# sockets.net
KiCad netlist of a schematic drawn in Altium Designer
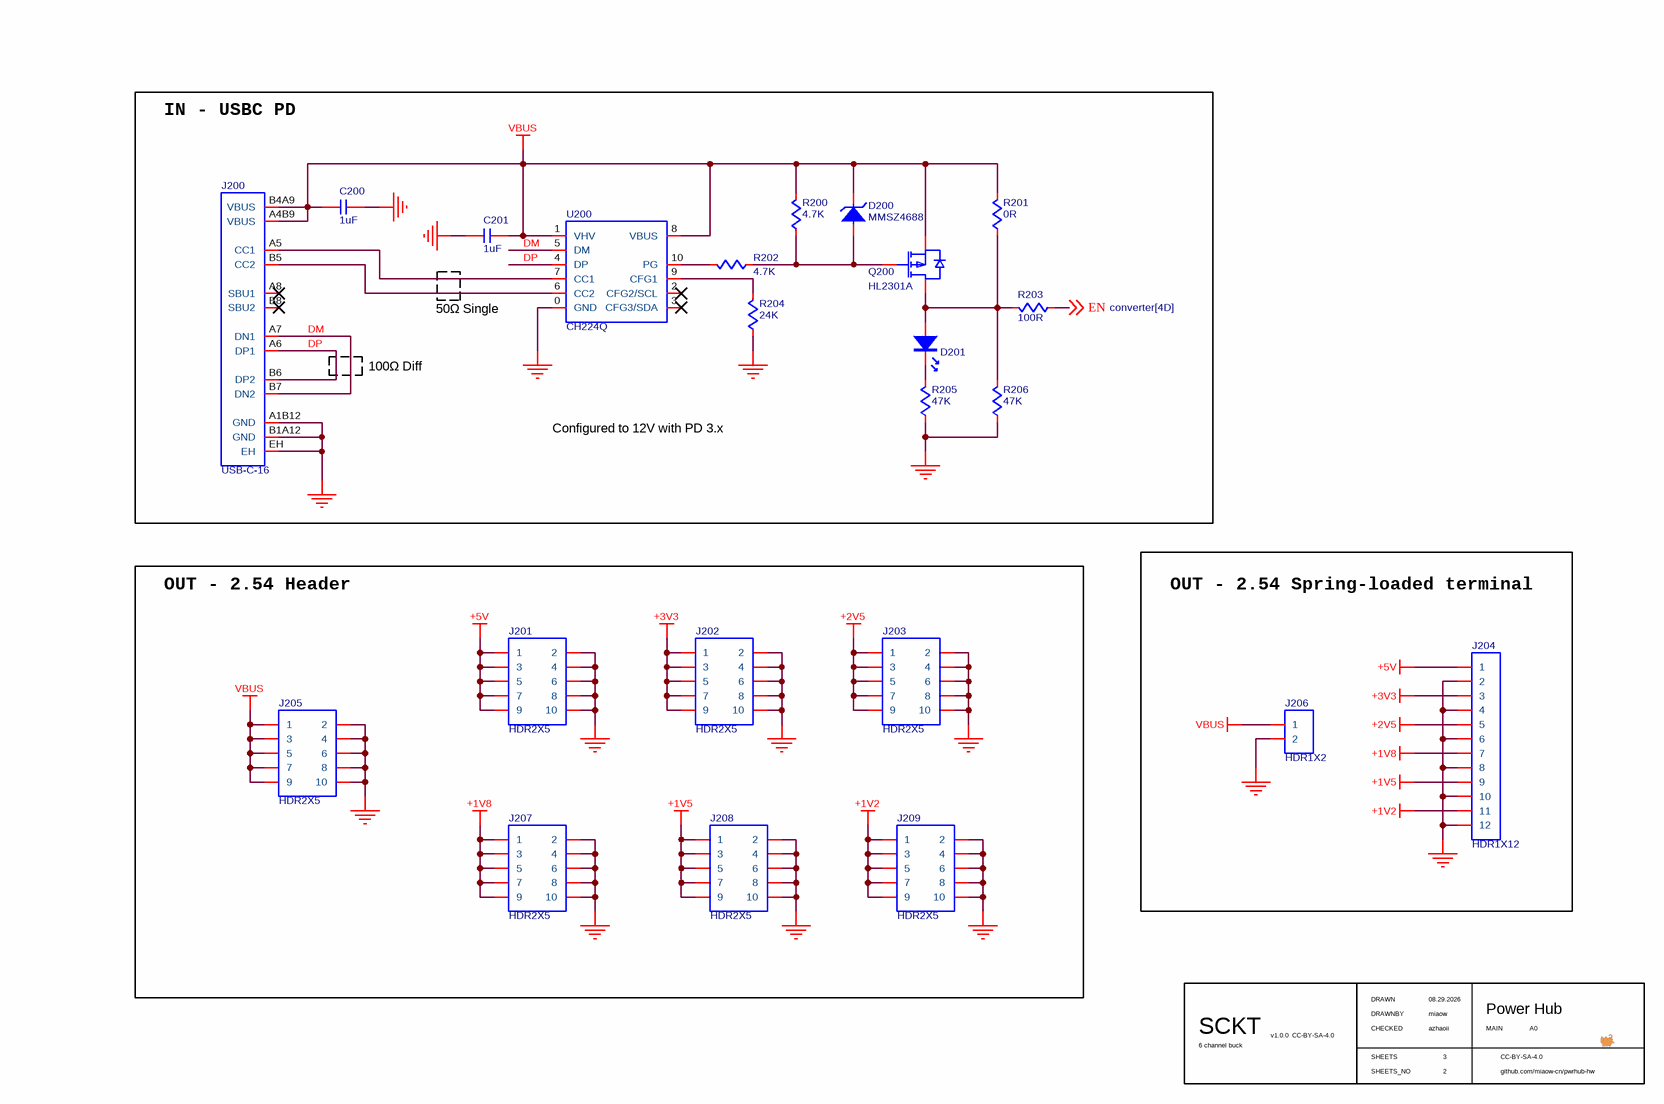
[diagram p0: sockets.schdoc]

(export (version "E")
  (design (tool "Eeschema 10.0.6"))
  (components
    (comp (ref "C200")
      (value "1uF")
      (footprint "mw:C0402")
      (fields (field (name "VOLTAGE") "25V") (field (name "Comment") "C-NOMO"))
      (libsource (lib "mw") (part "C-NOMO"))
    )
    (comp (ref "C201")
      (value "1uF")
      (footprint "mw:C0402")
      (fields (field (name "VOLTAGE") "25V") (field (name "Comment") "C-NOMO"))
      (libsource (lib "mw") (part "C-NOMO"))
    )
    (comp (ref "D200")
      (value "MMSZ4688")
      (footprint "mw:MMSZ4688")
      (description "ZENER")
      (libsource (lib "mw") (part "MMSZ4688"))
    )
    (comp (ref "D201") (value "LED") (footprint "mw:LED0603") (libsource (lib "mw") (part "LED")))
    (comp (ref "J200") (value "USB-C-16") (footprint "mw:USB-C-16") (libsource (lib "mw") (part "USB-C-16")))
    (comp (ref "J201") (value "HDR2X5") (footprint "mw:HDR2X5") (libsource (lib "mw") (part "HDR2X5")))
    (comp (ref "J202") (value "HDR2X5") (footprint "mw:HDR2X5") (libsource (lib "mw") (part "HDR2X5")))
    (comp (ref "J203") (value "HDR2X5") (footprint "mw:HDR2X5") (libsource (lib "mw") (part "HDR2X5")))
    (comp (ref "J204")
      (value "HDR1X12")
      (footprint "mw:KF141R-2.54-12P")
      (libsource (lib "mw") (part "HDR1X12"))
    )
    (comp (ref "J205") (value "HDR2X5") (footprint "mw:HDR2X5") (libsource (lib "mw") (part "HDR2X5")))
    (comp (ref "J206")
      (value "HDR1X2")
      (footprint "mw:KF141R-2.54-2P")
      (libsource (lib "mw") (part "HDR1X2"))
    )
    (comp (ref "J207") (value "HDR2X5") (footprint "mw:HDR2X5") (libsource (lib "mw") (part "HDR2X5")))
    (comp (ref "J208") (value "HDR2X5") (footprint "mw:HDR2X5") (libsource (lib "mw") (part "HDR2X5")))
    (comp (ref "J209") (value "HDR2X5") (footprint "mw:HDR2X5") (libsource (lib "mw") (part "HDR2X5")))
    (comp (ref "Q200")
      (value "HL2301A")
      (footprint "mw:HL2301A")
      (description "PMOS")
      (libsource (lib "mw") (part "HL2301A"))
    )
    (comp (ref "R200")
      (value "4.7K")
      (footprint "mw:R0402")
      (fields (field (name "Comment") "R"))
      (libsource (lib "mw") (part "R"))
    )
    (comp (ref "R201")
      (value "0R")
      (footprint "mw:R0402")
      (fields (field (name "Comment") "R"))
      (libsource (lib "mw") (part "R"))
    )
    (comp (ref "R202")
      (value "4.7K")
      (footprint "mw:R0402")
      (fields (field (name "Comment") "R"))
      (libsource (lib "mw") (part "R"))
    )
    (comp (ref "R203")
      (value "100R")
      (footprint "mw:R0402")
      (fields (field (name "Comment") "R"))
      (libsource (lib "mw") (part "R"))
    )
    (comp (ref "R204")
      (value "24K")
      (footprint "mw:R0402")
      (fields (field (name "Comment") "R"))
      (libsource (lib "mw") (part "R"))
    )
    (comp (ref "R205")
      (value "47K")
      (footprint "mw:R0402")
      (fields (field (name "Comment") "R"))
      (libsource (lib "mw") (part "R"))
    )
    (comp (ref "R206")
      (value "47K")
      (footprint "mw:R0402")
      (fields (field (name "Comment") "R"))
      (libsource (lib "mw") (part "R"))
    )
    (comp (ref "U200")
      (value "CH224Q")
      (footprint "mw:CH224Q")
      (description "PD3.2")
      (libsource (lib "mw") (part "CH224Q"))
    )
  )
  (nets
    (net (code "1") (name "+1V2") (class "Default")
      (node (ref "J204") (pin "11") (pinfunction "11_11") (pintype "passive"))
      (node (ref "J209") (pin "1") (pinfunction "1_1") (pintype "passive"))
      (node (ref "J209") (pin "3") (pinfunction "3_3") (pintype "passive"))
      (node (ref "J209") (pin "5") (pinfunction "5_5") (pintype "passive"))
      (node (ref "J209") (pin "7") (pinfunction "7_7") (pintype "passive"))
      (node (ref "J209") (pin "9") (pinfunction "9_9") (pintype "passive"))
    )
    (net (code "2") (name "+1V5") (class "Default")
      (node (ref "J204") (pin "9") (pinfunction "9_9") (pintype "passive"))
      (node (ref "J208") (pin "1") (pinfunction "1_1") (pintype "passive"))
      (node (ref "J208") (pin "3") (pinfunction "3_3") (pintype "passive"))
      (node (ref "J208") (pin "5") (pinfunction "5_5") (pintype "passive"))
      (node (ref "J208") (pin "7") (pinfunction "7_7") (pintype "passive"))
      (node (ref "J208") (pin "9") (pinfunction "9_9") (pintype "passive"))
    )
    (net (code "3") (name "+1V8") (class "Default")
      (node (ref "J204") (pin "7") (pinfunction "7_7") (pintype "passive"))
      (node (ref "J207") (pin "1") (pinfunction "1_1") (pintype "passive"))
      (node (ref "J207") (pin "3") (pinfunction "3_3") (pintype "passive"))
      (node (ref "J207") (pin "5") (pinfunction "5_5") (pintype "passive"))
      (node (ref "J207") (pin "7") (pinfunction "7_7") (pintype "passive"))
      (node (ref "J207") (pin "9") (pinfunction "9_9") (pintype "passive"))
    )
    (net (code "4") (name "+2V5") (class "Default")
      (node (ref "J203") (pin "1") (pinfunction "1_1") (pintype "passive"))
      (node (ref "J203") (pin "3") (pinfunction "3_3") (pintype "passive"))
      (node (ref "J203") (pin "5") (pinfunction "5_5") (pintype "passive"))
      (node (ref "J203") (pin "7") (pinfunction "7_7") (pintype "passive"))
      (node (ref "J203") (pin "9") (pinfunction "9_9") (pintype "passive"))
      (node (ref "J204") (pin "5") (pinfunction "5_5") (pintype "passive"))
    )
    (net (code "5") (name "+3V3") (class "Default")
      (node (ref "J202") (pin "1") (pinfunction "1_1") (pintype "passive"))
      (node (ref "J202") (pin "3") (pinfunction "3_3") (pintype "passive"))
      (node (ref "J202") (pin "5") (pinfunction "5_5") (pintype "passive"))
      (node (ref "J202") (pin "7") (pinfunction "7_7") (pintype "passive"))
      (node (ref "J202") (pin "9") (pinfunction "9_9") (pintype "passive"))
      (node (ref "J204") (pin "3") (pinfunction "3_3") (pintype "passive"))
    )
    (net (code "6") (name "+5V") (class "Default")
      (node (ref "J201") (pin "1") (pinfunction "1_1") (pintype "passive"))
      (node (ref "J201") (pin "3") (pinfunction "3_3") (pintype "passive"))
      (node (ref "J201") (pin "5") (pinfunction "5_5") (pintype "passive"))
      (node (ref "J201") (pin "7") (pinfunction "7_7") (pintype "passive"))
      (node (ref "J201") (pin "9") (pinfunction "9_9") (pintype "passive"))
      (node (ref "J204") (pin "1") (pinfunction "1_1") (pintype "passive"))
    )
    (net (code "7") (name "/DM") (class "Default")
      (node (ref "J200") (pin "A7") (pinfunction "DN1_A7") (pintype "passive"))
      (node (ref "J200") (pin "B7") (pinfunction "DN2_B7") (pintype "passive"))
      (node (ref "U200") (pin "5") (pinfunction "DM_5") (pintype "passive"))
    )
    (net (code "8") (name "/DP") (class "Default")
      (node (ref "J200") (pin "A6") (pinfunction "DP1_A6") (pintype "passive"))
      (node (ref "J200") (pin "B6") (pinfunction "DP2_B6") (pintype "passive"))
      (node (ref "U200") (pin "4") (pinfunction "DP_4") (pintype "passive"))
    )
    (net (code "9") (name "EN") (class "Default")
      (node (ref "R203") (pin "2") (pinfunction "2_2") (pintype "passive"))
    )
    (net (code "10") (name "GND") (class "Default")
      (node (ref "C200") (pin "1") (pinfunction "1_1") (pintype "passive"))
      (node (ref "C201") (pin "1") (pinfunction "1_1") (pintype "passive"))
      (node (ref "J200") (pin "A1B12") (pinfunction "GND_A1B12") (pintype "passive"))
      (node (ref "J200") (pin "B1A12") (pinfunction "GND_B1A12") (pintype "passive"))
      (node (ref "J200") (pin "EH") (pinfunction "EH_EH") (pintype "passive"))
      (node (ref "J201") (pin "10") (pinfunction "10_10") (pintype "passive"))
      (node (ref "J201") (pin "2") (pinfunction "2_2") (pintype "passive"))
      (node (ref "J201") (pin "4") (pinfunction "4_4") (pintype "passive"))
      (node (ref "J201") (pin "6") (pinfunction "6_6") (pintype "passive"))
      (node (ref "J201") (pin "8") (pinfunction "8_8") (pintype "passive"))
      (node (ref "J202") (pin "10") (pinfunction "10_10") (pintype "passive"))
      (node (ref "J202") (pin "2") (pinfunction "2_2") (pintype "passive"))
      (node (ref "J202") (pin "4") (pinfunction "4_4") (pintype "passive"))
      (node (ref "J202") (pin "6") (pinfunction "6_6") (pintype "passive"))
      (node (ref "J202") (pin "8") (pinfunction "8_8") (pintype "passive"))
      (node (ref "J203") (pin "10") (pinfunction "10_10") (pintype "passive"))
      (node (ref "J203") (pin "2") (pinfunction "2_2") (pintype "passive"))
      (node (ref "J203") (pin "4") (pinfunction "4_4") (pintype "passive"))
      (node (ref "J203") (pin "6") (pinfunction "6_6") (pintype "passive"))
      (node (ref "J203") (pin "8") (pinfunction "8_8") (pintype "passive"))
      (node (ref "J204") (pin "10") (pinfunction "10_10") (pintype "passive"))
      (node (ref "J204") (pin "12") (pinfunction "12_12") (pintype "passive"))
      (node (ref "J204") (pin "2") (pinfunction "2_2") (pintype "passive"))
      (node (ref "J204") (pin "4") (pinfunction "4_4") (pintype "passive"))
      (node (ref "J204") (pin "6") (pinfunction "6_6") (pintype "passive"))
      (node (ref "J204") (pin "8") (pinfunction "8_8") (pintype "passive"))
      (node (ref "J205") (pin "10") (pinfunction "10_10") (pintype "passive"))
      (node (ref "J205") (pin "2") (pinfunction "2_2") (pintype "passive"))
      (node (ref "J205") (pin "4") (pinfunction "4_4") (pintype "passive"))
      (node (ref "J205") (pin "6") (pinfunction "6_6") (pintype "passive"))
      (node (ref "J205") (pin "8") (pinfunction "8_8") (pintype "passive"))
      (node (ref "J206") (pin "2") (pinfunction "2_2") (pintype "passive"))
      (node (ref "J207") (pin "10") (pinfunction "10_10") (pintype "passive"))
      (node (ref "J207") (pin "2") (pinfunction "2_2") (pintype "passive"))
      (node (ref "J207") (pin "4") (pinfunction "4_4") (pintype "passive"))
      (node (ref "J207") (pin "6") (pinfunction "6_6") (pintype "passive"))
      (node (ref "J207") (pin "8") (pinfunction "8_8") (pintype "passive"))
      (node (ref "J208") (pin "10") (pinfunction "10_10") (pintype "passive"))
      (node (ref "J208") (pin "2") (pinfunction "2_2") (pintype "passive"))
      (node (ref "J208") (pin "4") (pinfunction "4_4") (pintype "passive"))
      (node (ref "J208") (pin "6") (pinfunction "6_6") (pintype "passive"))
      (node (ref "J208") (pin "8") (pinfunction "8_8") (pintype "passive"))
      (node (ref "J209") (pin "10") (pinfunction "10_10") (pintype "passive"))
      (node (ref "J209") (pin "2") (pinfunction "2_2") (pintype "passive"))
      (node (ref "J209") (pin "4") (pinfunction "4_4") (pintype "passive"))
      (node (ref "J209") (pin "6") (pinfunction "6_6") (pintype "passive"))
      (node (ref "J209") (pin "8") (pinfunction "8_8") (pintype "passive"))
      (node (ref "R204") (pin "2") (pinfunction "2_2") (pintype "passive"))
      (node (ref "R205") (pin "2") (pinfunction "2_2") (pintype "passive"))
      (node (ref "R206") (pin "2") (pinfunction "2_2") (pintype "passive"))
      (node (ref "U200") (pin "0") (pinfunction "GND_0") (pintype "passive"))
    )
    (net (code "11") (name "Net-(D200-A)") (class "Default")
      (node (ref "D200") (pin "2") (pinfunction "A_2") (pintype "passive"))
      (node (ref "Q200") (pin "G") (pinfunction "G_G") (pintype "passive"))
      (node (ref "R200") (pin "2") (pinfunction "2_2") (pintype "passive"))
      (node (ref "R202") (pin "2") (pinfunction "2_2") (pintype "passive"))
    )
    (net (code "12") (name "Net-(D201-Pad1)") (class "Default")
      (node (ref "D201") (pin "1") (pinfunction "1_1") (pintype "passive"))
      (node (ref "R205") (pin "1") (pinfunction "1_1") (pintype "passive"))
    )
    (net (code "13") (name "Net-(D201-Pad2)") (class "Default")
      (node (ref "D201") (pin "2") (pinfunction "2_2") (pintype "passive"))
      (node (ref "Q200") (pin "D") (pinfunction "D_D") (pintype "passive"))
      (node (ref "R201") (pin "2") (pinfunction "2_2") (pintype "passive"))
      (node (ref "R203") (pin "1") (pinfunction "1_1") (pintype "passive"))
      (node (ref "R206") (pin "1") (pinfunction "1_1") (pintype "passive"))
    )
    (net (code "14") (name "Net-(J200-CC1)") (class "Default")
      (node (ref "J200") (pin "A5") (pinfunction "CC1_A5") (pintype "passive"))
      (node (ref "U200") (pin "7") (pinfunction "CC1_7") (pintype "passive"))
    )
    (net (code "15") (name "Net-(J200-CC2)") (class "Default")
      (node (ref "J200") (pin "B5") (pinfunction "CC2_B5") (pintype "passive"))
      (node (ref "U200") (pin "6") (pinfunction "CC2_6") (pintype "passive"))
    )
    (net (code "16") (name "Net-(U200-CFG1)") (class "Default")
      (node (ref "R204") (pin "1") (pinfunction "1_1") (pintype "passive"))
      (node (ref "U200") (pin "9") (pinfunction "CFG1_9") (pintype "passive"))
    )
    (net (code "17") (name "Net-(U200-PG)") (class "Default")
      (node (ref "R202") (pin "1") (pinfunction "1_1") (pintype "passive"))
      (node (ref "U200") (pin "10") (pinfunction "PG_10") (pintype "passive"))
    )
    (net (code "18") (name "VBUS") (class "Default")
      (node (ref "C200") (pin "2") (pinfunction "2_2") (pintype "passive"))
      (node (ref "C201") (pin "2") (pinfunction "2_2") (pintype "passive"))
      (node (ref "D200") (pin "1") (pinfunction "C_1") (pintype "passive"))
      (node (ref "J200") (pin "A4B9") (pinfunction "VBUS_A4B9") (pintype "passive"))
      (node (ref "J200") (pin "B4A9") (pinfunction "VBUS_B4A9") (pintype "passive"))
      (node (ref "J205") (pin "1") (pinfunction "1_1") (pintype "passive"))
      (node (ref "J205") (pin "3") (pinfunction "3_3") (pintype "passive"))
      (node (ref "J205") (pin "5") (pinfunction "5_5") (pintype "passive"))
      (node (ref "J205") (pin "7") (pinfunction "7_7") (pintype "passive"))
      (node (ref "J205") (pin "9") (pinfunction "9_9") (pintype "passive"))
      (node (ref "J206") (pin "1") (pinfunction "1_1") (pintype "passive"))
      (node (ref "Q200") (pin "S") (pinfunction "S_S") (pintype "passive"))
      (node (ref "R200") (pin "1") (pinfunction "1_1") (pintype "passive"))
      (node (ref "R201") (pin "1") (pinfunction "1_1") (pintype "passive"))
      (node (ref "U200") (pin "1") (pinfunction "VHV_1") (pintype "passive"))
      (node (ref "U200") (pin "8") (pinfunction "VBUS_8") (pintype "passive"))
    )
    (net (code "19") (name "unconnected-(J200-SBU1-PadA8)") (class "Default")
      (node (ref "J200") (pin "A8") (pinfunction "SBU1_A8") (pintype "passive+no_connect"))
    )
    (net (code "20") (name "unconnected-(J200-SBU2-PadB8)") (class "Default")
      (node (ref "J200") (pin "B8") (pinfunction "SBU2_B8") (pintype "passive+no_connect"))
    )
    (net (code "21") (name "unconnected-(U200-CFG2{slash}SCL-Pad2)") (class "Default")
      (node (ref "U200") (pin "2") (pinfunction "CFG2/SCL_2") (pintype "passive+no_connect"))
    )
    (net (code "22") (name "unconnected-(U200-CFG3{slash}SDA-Pad3)") (class "Default")
      (node (ref "U200") (pin "3") (pinfunction "CFG3/SDA_3") (pintype "passive+no_connect"))
    )
  )
)
